# FIO_F.net
KiCad netlist of a schematic drawn in EAGLE
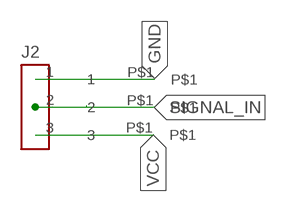
[diagram p0: schematic, sheet 1]

(export (version "E")
  (design (tool "Eeschema 10.0.6"))
  (components
    (comp (ref "J2")
      (value "CONECTOR_FEMEA")
      (footprint "eagle-import:3CONECTOR")
      (libsource (lib "eagle-import") (part "CONECTOR_FEMEA"))
    )
    (comp (ref "J4")
      (value "PAD")
      (footprint "eagle-import:PAD")
      (libsource (lib "eagle-import") (part "PAD"))
    )
    (comp (ref "U$1")
      (value "PAD")
      (footprint "eagle-import:PAD")
      (libsource (lib "eagle-import") (part "PAD"))
    )
    (comp (ref "VCC")
      (value "PAD")
      (footprint "eagle-import:PAD")
      (libsource (lib "eagle-import") (part "PAD"))
    )
  )
  (nets
    (net (code "1") (name "GND") (class "Default")
      (node (ref "J2") (pin "1") (pinfunction "1_1") (pintype "bidirectional"))
      (node (ref "U$1") (pin "P$1") (pinfunction "P$1_P$1") (pintype "bidirectional"))
    )
    (net (code "2") (name "SIGNAL_IN") (class "Default")
      (node (ref "J2") (pin "2") (pinfunction "2_2") (pintype "bidirectional"))
      (node (ref "J4") (pin "P$1") (pinfunction "P$1_P$1") (pintype "bidirectional"))
    )
    (net (code "3") (name "VCC") (class "Default")
      (node (ref "J2") (pin "3") (pinfunction "3_3") (pintype "bidirectional"))
      (node (ref "VCC") (pin "P$1") (pinfunction "P$1_P$1") (pintype "bidirectional"))
    )
  )
)
